# exp3.net
KiCad netlist of a schematic drawn in EAGLE
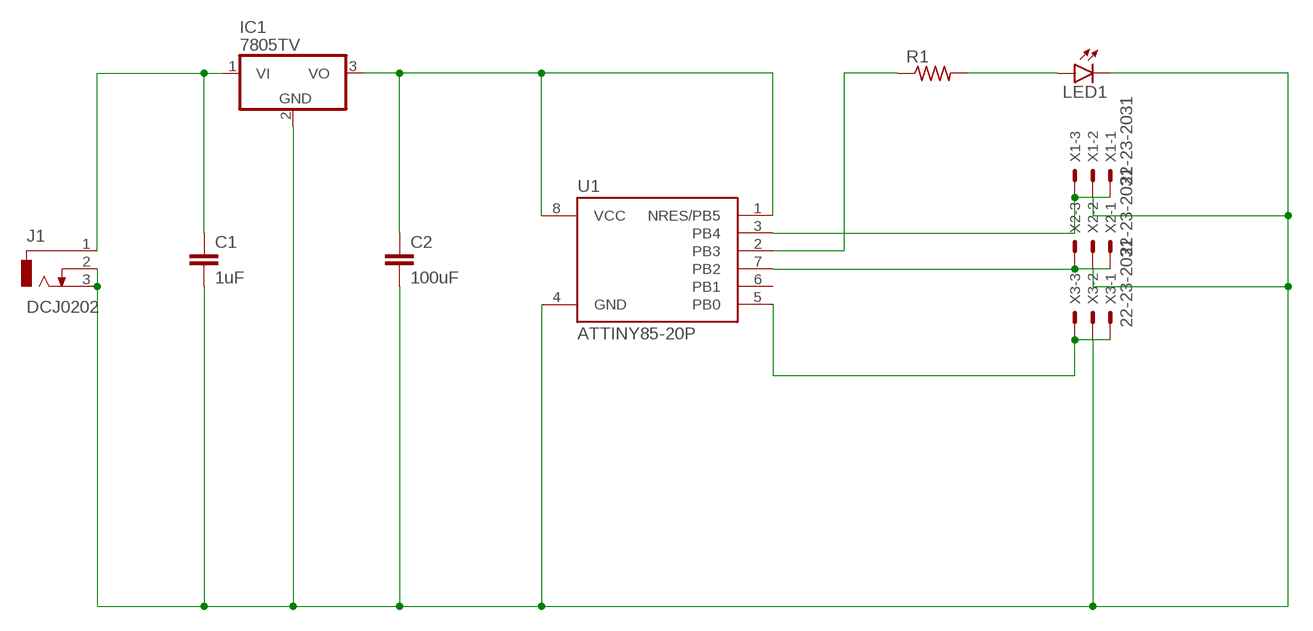
[diagram p0: schematic, sheet 1]

(export (version "E")
  (design (tool "Eeschema 10.0.6"))
  (components
    (comp (ref "C1")
      (value "1uF")
      (footprint "eagle-import:C2.5-3")
      (libsource (lib "eagle-import") (part "C2,5-3"))
    )
    (comp (ref "C2")
      (value "100uF")
      (footprint "eagle-import:C2.5-3")
      (libsource (lib "eagle-import") (part "C2,5-3"))
    )
    (comp (ref "IC1")
      (value "7805TV")
      (footprint "eagle-import:TO220V")
      (libsource (lib "eagle-import") (part "78TV05"))
    )
    (comp (ref "J1")
      (value "DCJ0202")
      (footprint "eagle-import:DCJ0202")
      (libsource (lib "eagle-import") (part "DCJ0202"))
    )
    (comp (ref "LED1")
      (value "LED10MM")
      (footprint "eagle-import:LED10MM")
      (libsource (lib "eagle-import") (part "LED10MM"))
    )
    (comp (ref "R1")
      (value "R-US_0207/10")
      (footprint "eagle-import:0207_10")
      (libsource (lib "eagle-import") (part "R-US_0207/10"))
    )
    (comp (ref "U1")
      (value "ATTINY85-20P")
      (footprint "eagle-import:PDIP08_300MIL")
      (libsource (lib "eagle-import") (part "ATTINY85P-20"))
    )
    (comp (ref "X1")
      (value "22-23-2031")
      (footprint "eagle-import:22-23-2031")
      (fields (field (name "MF") "MOLEX"))
      (libsource (lib "eagle-import") (part "22-23-2031"))
    )
    (comp (ref "X2")
      (value "22-23-2031")
      (footprint "eagle-import:22-23-2031")
      (fields (field (name "MF") "MOLEX"))
      (libsource (lib "eagle-import") (part "22-23-2031"))
    )
    (comp (ref "X3")
      (value "22-23-2031")
      (footprint "eagle-import:22-23-2031")
      (fields (field (name "MF") "MOLEX"))
      (libsource (lib "eagle-import") (part "22-23-2031"))
    )
  )
  (nets
    (net (code "1") (name "Net-(IC1-GND)") (class "Default")
      (node (ref "C1") (pin "2") (pinfunction "2_2") (pintype "passive"))
      (node (ref "C2") (pin "2") (pinfunction "2_2") (pintype "passive"))
      (node (ref "IC1") (pin "2") (pinfunction "GND_2") (pintype "passive"))
      (node (ref "J1") (pin "2") (pinfunction "2_2") (pintype "passive"))
      (node (ref "J1") (pin "3") (pinfunction "3_3") (pintype "passive"))
      (node (ref "LED1") (pin "K") (pinfunction "C_K") (pintype "passive"))
      (node (ref "U1") (pin "4") (pinfunction "GND_4") (pintype "power_in"))
      (node (ref "X1") (pin "2") (pinfunction "S_2") (pintype "passive"))
      (node (ref "X2") (pin "2") (pinfunction "S_2") (pintype "passive"))
      (node (ref "X3") (pin "2") (pinfunction "S_2") (pintype "passive"))
    )
    (net (code "2") (name "Net-(IC1-VI)") (class "Default")
      (node (ref "C1") (pin "1") (pinfunction "1_1") (pintype "passive"))
      (node (ref "IC1") (pin "1") (pinfunction "VI_1") (pintype "input"))
      (node (ref "J1") (pin "1") (pinfunction "1_1") (pintype "passive"))
    )
    (net (code "3") (name "Net-(IC1-VO)") (class "Default")
      (node (ref "C2") (pin "1") (pinfunction "1_1") (pintype "passive"))
      (node (ref "IC1") (pin "3") (pinfunction "VO_3") (pintype "passive"))
      (node (ref "U1") (pin "1") (pinfunction "NRES/PB5_1") (pintype "bidirectional"))
      (node (ref "U1") (pin "8") (pinfunction "VCC_8") (pintype "power_in"))
    )
    (net (code "4") (name "Net-(LED1-PadA)") (class "Default")
      (node (ref "LED1") (pin "A") (pinfunction "A_A") (pintype "passive"))
      (node (ref "R1") (pin "2") (pinfunction "2_2") (pintype "passive"))
    )
    (net (code "5") (name "Net-(U1-PB0)") (class "Default")
      (node (ref "U1") (pin "5") (pinfunction "PB0_5") (pintype "bidirectional"))
      (node (ref "X3") (pin "1") (pinfunction "S_1") (pintype "passive"))
      (node (ref "X3") (pin "3") (pinfunction "S_3") (pintype "passive"))
    )
    (net (code "6") (name "Net-(U1-PB2)") (class "Default")
      (node (ref "U1") (pin "7") (pinfunction "PB2_7") (pintype "bidirectional"))
      (node (ref "X2") (pin "1") (pinfunction "S_1") (pintype "passive"))
      (node (ref "X2") (pin "3") (pinfunction "S_3") (pintype "passive"))
    )
    (net (code "7") (name "Net-(U1-PB3)") (class "Default")
      (node (ref "R1") (pin "1") (pinfunction "1_1") (pintype "passive"))
      (node (ref "U1") (pin "2") (pinfunction "PB3_2") (pintype "bidirectional"))
    )
    (net (code "8") (name "Net-(U1-PB4)") (class "Default")
      (node (ref "U1") (pin "3") (pinfunction "PB4_3") (pintype "bidirectional"))
      (node (ref "X1") (pin "1") (pinfunction "S_1") (pintype "passive"))
      (node (ref "X1") (pin "3") (pinfunction "S_3") (pintype "passive"))
    )
    (net (code "9") (name "unconnected-(U1-PB1-Pad6)") (class "Default")
      (node (ref "U1") (pin "6") (pinfunction "PB1_6") (pintype "bidirectional"))
    )
  )
)
